# STM32F446RE_board.net
KiCad netlist of a schematic drawn in Altium Designer
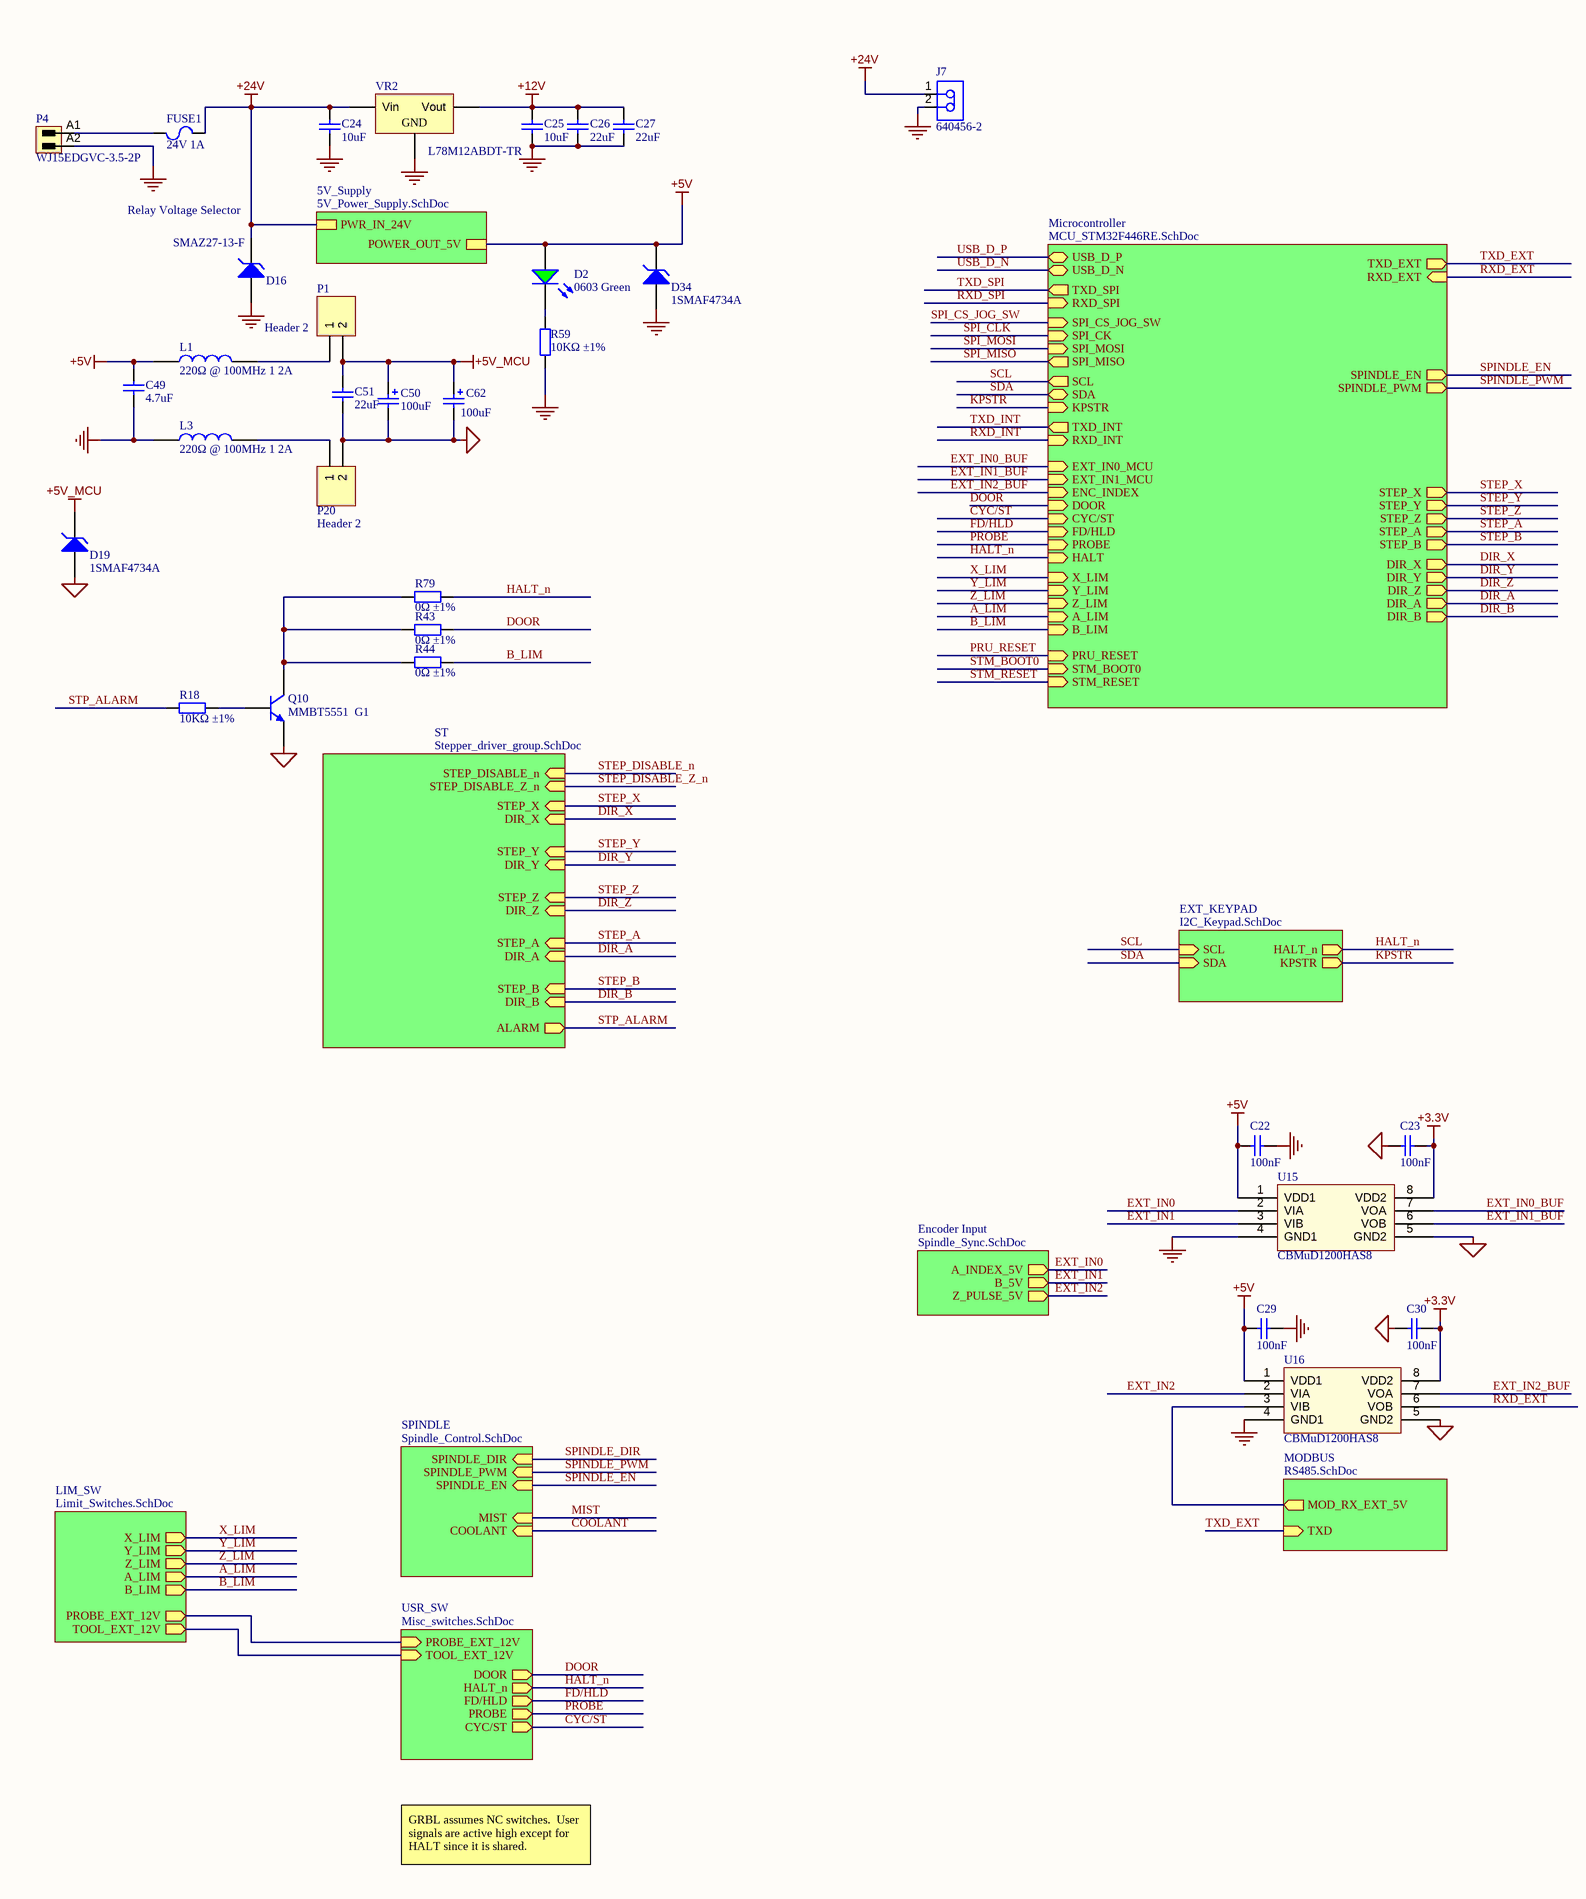
[diagram p0: STM32F446RE_board.SchDoc, left]
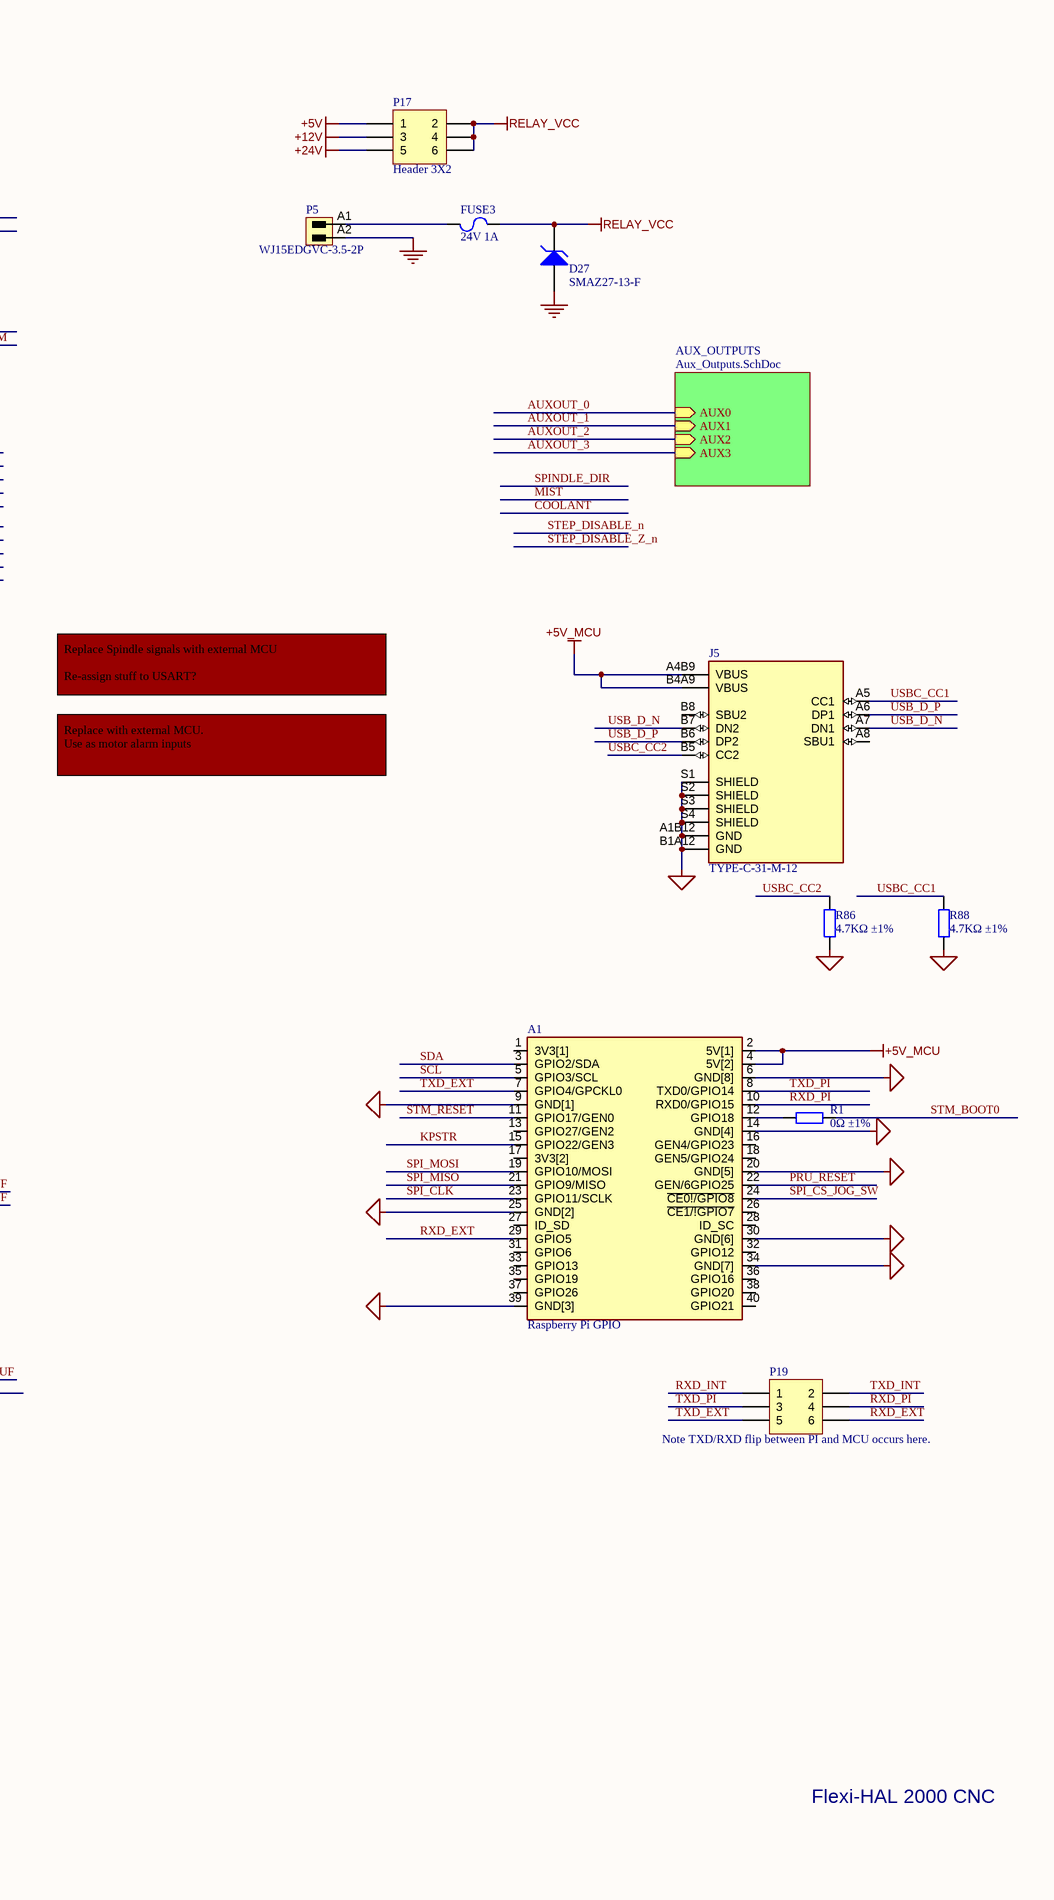
[diagram p1: STM32F446RE_board.SchDoc, right]

(export (version "E")
  (design (tool "Eeschema 10.0.6"))
  (components
    (comp (ref "A1")
      (value "Raspberry Pi GPIO")
      (footprint "MODULE_RASPBERRY_PI_4_MODEL_B")
      (description "Raspberry Pi Zero WH _Zero W with Headers_")
      (fields (field (name "MP") "DS1023-2*20SF11") (field (name "MF") "CONNFLY Elec"))
      (libsource (lib "Universal_CNC_Breakout") (part "ADA3708"))
    )
    (comp (ref "C22")
      (value "100nF")
      (footprint "0603_C")
      (description "Chip capacitors")
      (fields (field (name "MANUFACTURER") "YAGEO") (field (name "PARTNUMBER") "CC0603KRX7R9BB104"))
      (libsource (lib "Cap") (part "0603 100nF (104) 10% 50V"))
    )
    (comp (ref "C23")
      (value "100nF")
      (footprint "0603_C")
      (description "Chip capacitors")
      (fields (field (name "MANUFACTURER") "YAGEO") (field (name "PARTNUMBER") "CC0603KRX7R9BB104"))
      (libsource (lib "Cap") (part "0603 100nF (104) 10% 50V"))
    )
    (comp (ref "C24")
      (value "10uF")
      (footprint "1206_C")
      (description "Chip capacitors")
      (fields
        (field (name "MANUFACTURER") "Samsung Electro-Mechanics")
        (field (name "PARTNUMBER") "CL31A106KBHNNNE")
      )
      (libsource (lib "Cap") (part "1206 10uF (106) 10% 50V"))
    )
    (comp (ref "C25")
      (value "10uF")
      (footprint "1206_C")
      (description "Chip capacitors")
      (fields
        (field (name "MANUFACTURER") "Samsung Electro-Mechanics")
        (field (name "PARTNUMBER") "CL31A106KBHNNNE")
      )
      (libsource (lib "Cap") (part "1206 10uF (106) 10% 50V"))
    )
    (comp (ref "C26")
      (value "22uF")
      (footprint "0805_C")
      (description "Chip capacitors")
      (fields
        (field (name "MANUFACTURER") "Samsung Electro-Mechanics")
        (field (name "PARTNUMBER") "CL21A226MAQNNNE")
      )
      (libsource (lib "Cap") (part "0805 22uF (226) 20% 25V"))
    )
    (comp (ref "C27")
      (value "22uF")
      (footprint "0805_C")
      (description "Chip capacitors")
      (fields
        (field (name "MANUFACTURER") "Samsung Electro-Mechanics")
        (field (name "PARTNUMBER") "CL21A226MAQNNNE")
      )
      (libsource (lib "Cap") (part "0805 22uF (226) 20% 25V"))
    )
    (comp (ref "C29")
      (value "100nF")
      (footprint "0603_C")
      (description "Chip capacitors")
      (fields (field (name "MANUFACTURER") "YAGEO") (field (name "PARTNUMBER") "CC0603KRX7R9BB104"))
      (libsource (lib "Cap") (part "0603 100nF (104) 10% 50V"))
    )
    (comp (ref "C30")
      (value "100nF")
      (footprint "0603_C")
      (description "Chip capacitors")
      (fields (field (name "MANUFACTURER") "YAGEO") (field (name "PARTNUMBER") "CC0603KRX7R9BB104"))
      (libsource (lib "Cap") (part "0603 100nF (104) 10% 50V"))
    )
    (comp (ref "C49")
      (value "4.7uF")
      (footprint "0603_C")
      (description "Chip capacitors")
      (fields
        (field (name "MANUFACTURER") "Samsung Electro-Mechanics")
        (field (name "PARTNUMBER") "CL10A475KO8NNNC")
      )
      (libsource (lib "Cap") (part "0603 4.7uF (475) 10% 16V"))
    )
    (comp (ref "C50")
      (value "100uF")
      (footprint "CASE-B_3528")
      (description "Tantalum capacitor")
      (fields (field (name "MANUFACTURER") "AVX") (field (name "PARTNUMBER") "TAJB107K006RNJ"))
      (libsource (lib "Cap") (part "3528 100uF (107) 10% 6.3V"))
    )
    (comp (ref "C51")
      (value "22uF")
      (footprint "0805_C")
      (description "Chip capacitors")
      (fields
        (field (name "MANUFACTURER") "Samsung Electro-Mechanics")
        (field (name "PARTNUMBER") "CL21A226MAQNNNE")
      )
      (libsource (lib "Cap") (part "0805 22uF (226) 20% 25V"))
    )
    (comp (ref "C62")
      (value "100uF")
      (footprint "WCAP-ASLI_D6.3H7.7")
      (fields (field (name "MANUFACTURER") "Capxon International Elec"))
      (libsource (lib "IQAnalog") (part "865080445010"))
    )
    (comp (ref "D2")
      (value "0603 Green")
      (footprint "0603_LED_S1")
      (description "LED")
      (libsource (lib "LED") (part "0603 LED Green"))
    )
    (comp (ref "D16")
      (value "SMAZ27-13-F")
      (footprint "DIOM5226X240N")
      (description "27V ±5% 1W 500nA @ 20.5V SMA(DO-214AC) Zener Diodes RoHS")
      (libsource (lib "PrintNC_GRBLHAL_Breakout") (part "BZT52C27"))
    )
    (comp (ref "D19")
      (value "1SMAF4734A")
      (footprint "DIOM5226X240N")
      (description "27V ±5% 1W 500nA @ 20.5V SMA(DO-214AC) Zener Diodes RoHS")
      (libsource (lib "PrintNC_GRBLHAL_Breakout") (part "BZT52C27"))
    )
    (comp (ref "D27")
      (value "SMAZ27-13-F")
      (footprint "DIOM5226X240N")
      (description "27V ±5% 1W 500nA @ 20.5V SMA(DO-214AC) Zener Diodes RoHS")
      (libsource (lib "PrintNC_GRBLHAL_Breakout") (part "BZT52C27"))
    )
    (comp (ref "D34")
      (value "1SMAF4734A")
      (footprint "DIOM5226X240N")
      (description "27V ±5% 1W 500nA @ 20.5V SMA(DO-214AC) Zener Diodes RoHS")
      (libsource (lib "PrintNC_GRBLHAL_Breakout") (part "BZT52C27"))
    )
    (comp (ref "FUSE1")
      (value "24V 1A")
      (footprint "1206_C")
      (description "24V 1A 0.1s 1206 PTC Resettable Fuses RoHS")
      (fields
        (field (name "MANUFACTURER") "Jinrui Electronic Materials Co.")
        (field (name "PARTNUMBER") "JK-nSMD050-24")
      )
      (libsource (lib "PrintNC_GRBLHAL_Breakout") (part "JK-nSMD050-24"))
    )
    (comp (ref "FUSE3")
      (value "24V 1A")
      (footprint "1206_C")
      (description "24V 1A 0.1s 1206 PTC Resettable Fuses RoHS")
      (fields
        (field (name "MANUFACTURER") "Jinrui Electronic Materials Co.")
        (field (name "PARTNUMBER") "JK-nSMD050-24")
      )
      (libsource (lib "PrintNC_GRBLHAL_Breakout") (part "JK-nSMD050-24"))
    )
    (comp (ref "J5")
      (value "TYPE-C-31-M-12")
      (footprint "HRO_TYPE-C-31-M-12")
      (description "USB Connectors 24 Receptacle 1 8.94*7.3mm RoHS")
      (fields (field (name "MF") "HRO Electronics Co., Ltd."))
      (libsource (lib "Universal_CNC_Breakout") (part "TYPE-C-31-M-12"))
    )
    (comp (ref "J7")
      (value "640456-2")
      (footprint "TECO-640456-2_V")
      (fields (field (name "MANUFACTURER") "TE Connectivity"))
      (libsource (lib "Altium Content Vault") (part "CN-2P-F-QF2"))
    )
    (comp (ref "L1")
      (value "220Ω @ 100MHz 1 2A")
      (footprint "0805_C")
      (description "220Ω @ 100MHz 1 2A 150mΩ 0805 Ferrite Beads ROHS")
      (libsource (lib "FBEAD") (part "0402 220R@100Mhz 0.1A"))
    )
    (comp (ref "L3")
      (value "220Ω @ 100MHz 1 2A")
      (footprint "0805_C")
      (description "220Ω @ 100MHz 1 2A 150mΩ 0805 Ferrite Beads ROHS")
      (libsource (lib "FBEAD") (part "0402 220R@100Mhz 0.1A"))
    )
    (comp (ref "P1")
      (value "Header 2")
      (footprint "HDR1X2")
      (description "Header, 2-Pin")
      (fields (field (name "PUBLISHER") "Altium Limited"))
      (libsource (lib "Miscellaneous Connectors") (part "Header 2"))
    )
    (comp (ref "P4")
      (value "WJ15EDGVC-3.5-2P")
      (footprint "691321100002")
      (libsource (lib "Universal_CNC_Breakout") (part "3.5mm Terminal Header 2p"))
    )
    (comp (ref "P5")
      (value "WJ15EDGVC-3.5-2P")
      (footprint "691321100002")
      (fields (field (name "MANUFACTURER") "Weidmueller"))
      (libsource (lib "Universal_CNC_Breakout") (part "3.5mm Terminal Header 2p"))
    )
    (comp (ref "P17")
      (value "Header 3X2")
      (footprint "HDR2X3")
      (description "Header, 3-Pin, Dual row")
      (fields (field (name "PUBLISHER") "Altium Limited"))
      (libsource (lib "Miscellaneous Connectors") (part "Header 3X2"))
    )
    (comp (ref "P19")
      (value "Header 3X2")
      (footprint "HDR2X3")
      (description "Header, 3-Pin, Dual row")
      (fields (field (name "PUBLISHER") "Altium Limited"))
      (libsource (lib "Miscellaneous Connectors") (part "Header 3X2"))
    )
    (comp (ref "P20")
      (value "Header 2")
      (footprint "HDR1X2")
      (description "Header, 2-Pin")
      (fields (field (name "PUBLISHER") "Altium Limited"))
      (libsource (lib "") (part "Header 2_1"))
    )
    (comp (ref "Q10")
      (value "MMBT5551  G1")
      (footprint "SOT-23(SOT-23-3)")
      (description "三极管")
      (libsource (lib "PrintNC_GRBLHAL_Breakout") (part "SOT-23 MMBT5551  G1"))
    )
    (comp (ref "R1")
      (value "0Ω ±1%")
      (footprint "0603_R")
      (description "Chip resistor")
      (fields (field (name "MANUFACTURER") "Uniroyal Elec") (field (name "PARTNUMBER") "0603WAF0000T5E"))
      (libsource (lib "RES") (part "0603 0R (0R0) 1%"))
    )
    (comp (ref "R18")
      (value "10KΩ ±1%")
      (footprint "0603_R")
      (description "Chip resistor")
      (fields (field (name "MANUFACTURER") "Uniroyal Elec") (field (name "PARTNUMBER") "0603WAF1002T5E"))
      (libsource (lib "RES") (part "0603 10K (1002) 1%"))
    )
    (comp (ref "R43")
      (value "0Ω ±1%")
      (footprint "0603_R")
      (description "Chip resistor")
      (fields (field (name "MANUFACTURER") "Uniroyal Elec") (field (name "PARTNUMBER") "0603WAF0000T5E"))
      (libsource (lib "RES") (part "0603 0R (0R0) 1%"))
    )
    (comp (ref "R44")
      (value "0Ω ±1%")
      (footprint "0603_R")
      (description "Chip resistor")
      (fields (field (name "MANUFACTURER") "Uniroyal Elec") (field (name "PARTNUMBER") "0603WAF0000T5E"))
      (libsource (lib "RES") (part "0603 0R (0R0) 1%"))
    )
    (comp (ref "R59")
      (value "10KΩ ±1%")
      (footprint "0603_R")
      (description "Chip resistor")
      (fields (field (name "MANUFACTURER") "Uniroyal Elec") (field (name "PARTNUMBER") "0603WAF1002T5E"))
      (libsource (lib "") (part "0603 10K (1002) 1%_1"))
    )
    (comp (ref "R79")
      (value "0Ω ±1%")
      (footprint "0603_R")
      (description "Chip resistor")
      (fields (field (name "MANUFACTURER") "Uniroyal Elec") (field (name "PARTNUMBER") "0603WAF0000T5E"))
      (libsource (lib "RES") (part "0603 0R (0R0) 1%"))
    )
    (comp (ref "R86")
      (value "4.7KΩ ±1%")
      (footprint "0603_R")
      (description "Chip resistor")
      (fields (field (name "MANUFACTURER") "Uniroyal Elec") (field (name "PARTNUMBER") "0603WAF4701T5E"))
      (libsource (lib "RES") (part "0603 4.7K (4701) 1%"))
    )
    (comp (ref "R88")
      (value "4.7KΩ ±1%")
      (footprint "0603_R")
      (description "Chip resistor")
      (fields (field (name "MANUFACTURER") "Uniroyal Elec") (field (name "PARTNUMBER") "0603WAF4701T5E"))
      (libsource (lib "RES") (part "0603 4.7K (4701) 1%"))
    )
    (comp (ref "U15")
      (value "CBMuD1200HAS8")
      (footprint "SOIC-8_150mil")
      (description "Dual Channel Isolator")
      (libsource (lib "IC") (part "ADUM1201ARZ-RL7_[C9669]"))
    )
    (comp (ref "U16")
      (value "CBMuD1200HAS8")
      (footprint "SOIC-8_150mil")
      (description "Dual Channel Isolator")
      (libsource (lib "IC") (part "ADUM1201ARZ-RL7_[C9669]"))
    )
    (comp (ref "VR2")
      (value "L78M12ABDT-TR")
      (footprint "TO-252-2-180")
      (libsource (lib "PrintNC_GRBLHAL_Breakout") (part "TO-252-2 L78M05ABDT-TR"))
    )
  )
  (nets
    (net (code "1") (name "+3.3V") (class "Default")
      (node (ref "C23") (pin "2") (pinfunction "2_2") (pintype "passive"))
      (node (ref "C30") (pin "2") (pinfunction "2_2") (pintype "passive"))
      (node (ref "U15") (pin "8") (pinfunction "VDD2_8") (pintype "passive"))
      (node (ref "U16") (pin "8") (pinfunction "VDD2_8") (pintype "passive"))
    )
    (net (code "2") (name "+5V") (class "Default")
      (node (ref "C22") (pin "1") (pinfunction "1_1") (pintype "passive"))
      (node (ref "C29") (pin "1") (pinfunction "1_1") (pintype "passive"))
      (node (ref "C49") (pin "2") (pinfunction "2_2") (pintype "passive"))
      (node (ref "D2") (pin "A") (pinfunction "A_A") (pintype "passive"))
      (node (ref "D34") (pin "2") (pinfunction "K_2") (pintype "passive"))
      (node (ref "L1") (pin "1") (pinfunction "1_1") (pintype "passive"))
      (node (ref "P17") (pin "1") (pinfunction "1_1") (pintype "passive"))
      (node (ref "U15") (pin "1") (pinfunction "VDD1_1") (pintype "passive"))
      (node (ref "U16") (pin "1") (pinfunction "VDD1_1") (pintype "passive"))
    )
    (net (code "3") (name "+5V_MCU") (class "Default")
      (node (ref "A1") (pin "2") (pinfunction "5V[1]_2") (pintype "power_in"))
      (node (ref "A1") (pin "4") (pinfunction "5V[2]_4") (pintype "power_in"))
      (node (ref "C50") (pin "1") (pinfunction "1_1") (pintype "passive"))
      (node (ref "C51") (pin "2") (pinfunction "2_2") (pintype "passive"))
      (node (ref "C62") (pin "1") (pinfunction "P_1") (pintype "passive"))
      (node (ref "D19") (pin "2") (pinfunction "K_2") (pintype "passive"))
      (node (ref "J5") (pin "A4B9") (pinfunction "VBUS_A4B9") (pintype "power_in"))
      (node (ref "J5") (pin "B4A9") (pinfunction "VBUS_B4A9") (pintype "power_in"))
      (node (ref "P1") (pin "2") (pinfunction "2_2") (pintype "passive"))
    )
    (net (code "4") (name "+12V") (class "Default")
      (node (ref "C25") (pin "2") (pinfunction "2_2") (pintype "passive"))
      (node (ref "C26") (pin "2") (pinfunction "2_2") (pintype "passive"))
      (node (ref "C27") (pin "2") (pinfunction "2_2") (pintype "passive"))
      (node (ref "P17") (pin "3") (pinfunction "3_3") (pintype "passive"))
      (node (ref "VR2") (pin "3") (pinfunction "Vout_3") (pintype "passive"))
    )
    (net (code "5") (name "+24V") (class "Default")
      (node (ref "C24") (pin "2") (pinfunction "2_2") (pintype "passive"))
      (node (ref "D16") (pin "2") (pinfunction "K_2") (pintype "passive"))
      (node (ref "FUSE1") (pin "2") (pinfunction "2_2") (pintype "passive"))
      (node (ref "J7") (pin "1") (pinfunction "1_1") (pintype "passive"))
      (node (ref "P17") (pin "5") (pinfunction "5_5") (pintype "passive"))
      (node (ref "VR2") (pin "1") (pinfunction "Vin_1") (pintype "passive"))
    )
    (net (code "11") (name "/B_LIM") (class "Default")
      (node (ref "R44") (pin "1") (pinfunction "1_1") (pintype "passive"))
    )
    (net (code "19") (name "/DOOR") (class "Default")
      (node (ref "R43") (pin "1") (pinfunction "1_1") (pintype "passive"))
    )
    (net (code "20") (name "/EXT_IN0") (class "Default")
      (node (ref "U15") (pin "2") (pinfunction "VIA_2") (pintype "passive"))
    )
    (net (code "21") (name "/EXT_IN0_BUF") (class "Default")
      (node (ref "U15") (pin "7") (pinfunction "VOA_7") (pintype "passive"))
    )
    (net (code "22") (name "/EXT_IN1") (class "Default")
      (node (ref "U15") (pin "3") (pinfunction "VIB_3") (pintype "passive"))
    )
    (net (code "23") (name "/EXT_IN1_BUF") (class "Default")
      (node (ref "U15") (pin "6") (pinfunction "VOB_6") (pintype "passive"))
    )
    (net (code "24") (name "/EXT_IN2") (class "Default")
      (node (ref "U16") (pin "2") (pinfunction "VIA_2") (pintype "passive"))
    )
    (net (code "25") (name "/EXT_IN2_BUF") (class "Default")
      (node (ref "U16") (pin "7") (pinfunction "VOA_7") (pintype "passive"))
    )
    (net (code "27") (name "/HALT_n") (class "Default")
      (node (ref "R79") (pin "1") (pinfunction "1_1") (pintype "passive"))
    )
    (net (code "28") (name "/KPSTR") (class "Default")
      (node (ref "A1") (pin "15") (pinfunction "GPIO22/GEN3_15") (pintype "bidirectional"))
    )
    (net (code "30") (name "/MOD_RX_EXT_5V") (class "Default")
      (node (ref "U16") (pin "3") (pinfunction "VIB_3") (pintype "passive"))
    )
    (net (code "33") (name "/PRU_RESET") (class "Default")
      (node (ref "A1") (pin "22") (pinfunction "GEN/6GPIO25_22") (pintype "bidirectional"))
    )
    (net (code "34") (name "/RXD_EXT") (class "Default")
      (node (ref "A1") (pin "29") (pinfunction "GPIO5_29") (pintype "bidirectional"))
      (node (ref "P19") (pin "6") (pinfunction "6_6") (pintype "passive"))
      (node (ref "U16") (pin "6") (pinfunction "VOB_6") (pintype "passive"))
    )
    (net (code "35") (name "/RXD_INT") (class "Default")
      (node (ref "P19") (pin "1") (pinfunction "1_1") (pintype "passive"))
    )
    (net (code "36") (name "/RXD_PI") (class "Default")
      (node (ref "A1") (pin "10") (pinfunction "RXD0/GPIO15_10") (pintype "bidirectional"))
      (node (ref "P19") (pin "4") (pinfunction "4_4") (pintype "passive"))
    )
    (net (code "38") (name "/SCL") (class "Default")
      (node (ref "A1") (pin "5") (pinfunction "GPIO3/SCL_5") (pintype "bidirectional"))
    )
    (net (code "39") (name "/SDA") (class "Default")
      (node (ref "A1") (pin "3") (pinfunction "GPIO2/SDA_3") (pintype "bidirectional"))
    )
    (net (code "43") (name "/SPI_CLK") (class "Default")
      (node (ref "A1") (pin "23") (pinfunction "GPIO11/SCLK_23") (pintype "bidirectional"))
    )
    (net (code "44") (name "/SPI_CS_JOG_SW") (class "Default")
      (node (ref "A1") (pin "24") (pinfunction "~{CE0!/GPIO8}_24") (pintype "bidirectional"))
    )
    (net (code "45") (name "/SPI_MISO") (class "Default")
      (node (ref "A1") (pin "21") (pinfunction "GPIO9/MISO_21") (pintype "bidirectional"))
    )
    (net (code "46") (name "/SPI_MOSI") (class "Default")
      (node (ref "A1") (pin "19") (pinfunction "GPIO10/MOSI_19") (pintype "bidirectional"))
    )
    (net (code "54") (name "/STM_BOOT0") (class "Default")
      (node (ref "R1") (pin "1") (pinfunction "1_1") (pintype "passive"))
    )
    (net (code "55") (name "/STM_RESET") (class "Default")
      (node (ref "A1") (pin "11") (pinfunction "GPIO17/GEN0_11") (pintype "bidirectional"))
    )
    (net (code "56") (name "/STP_ALARM") (class "Default")
      (node (ref "R18") (pin "2") (pinfunction "2_2") (pintype "passive"))
    )
    (net (code "58") (name "/TXD_EXT") (class "Default")
      (node (ref "A1") (pin "7") (pinfunction "GPIO4/GPCKL0_7") (pintype "bidirectional"))
      (node (ref "P19") (pin "5") (pinfunction "5_5") (pintype "passive"))
    )
    (net (code "59") (name "/TXD_INT") (class "Default")
      (node (ref "P19") (pin "2") (pinfunction "2_2") (pintype "passive"))
    )
    (net (code "60") (name "/TXD_PI") (class "Default")
      (node (ref "A1") (pin "8") (pinfunction "TXD0/GPIO14_8") (pintype "bidirectional"))
      (node (ref "P19") (pin "3") (pinfunction "3_3") (pintype "passive"))
    )
    (net (code "62") (name "/USBC_CC1") (class "Default")
      (node (ref "J5") (pin "A5") (pinfunction "CC1_A5") (pintype "bidirectional"))
      (node (ref "R88") (pin "1") (pinfunction "1_1") (pintype "passive"))
    )
    (net (code "63") (name "/USBC_CC2") (class "Default")
      (node (ref "J5") (pin "B5") (pinfunction "CC2_B5") (pintype "bidirectional"))
      (node (ref "R86") (pin "1") (pinfunction "1_1") (pintype "passive"))
    )
    (net (code "64") (name "/USB_D_N") (class "Default")
      (node (ref "J5") (pin "A7") (pinfunction "DN1_A7") (pintype "bidirectional"))
      (node (ref "J5") (pin "B7") (pinfunction "DN2_B7") (pintype "bidirectional"))
    )
    (net (code "65") (name "/USB_D_P") (class "Default")
      (node (ref "J5") (pin "A6") (pinfunction "DP1_A6") (pintype "bidirectional"))
      (node (ref "J5") (pin "B6") (pinfunction "DP2_B6") (pintype "bidirectional"))
    )
    (net (code "69") (name "GND") (class "Default")
      (node (ref "C22") (pin "2") (pinfunction "2_2") (pintype "passive"))
      (node (ref "C24") (pin "1") (pinfunction "1_1") (pintype "passive"))
      (node (ref "C25") (pin "1") (pinfunction "1_1") (pintype "passive"))
      (node (ref "C26") (pin "1") (pinfunction "1_1") (pintype "passive"))
      (node (ref "C27") (pin "1") (pinfunction "1_1") (pintype "passive"))
      (node (ref "C29") (pin "2") (pinfunction "2_2") (pintype "passive"))
      (node (ref "C49") (pin "1") (pinfunction "1_1") (pintype "passive"))
      (node (ref "D16") (pin "1") (pinfunction "A_1") (pintype "passive"))
      (node (ref "D27") (pin "1") (pinfunction "A_1") (pintype "passive"))
      (node (ref "D34") (pin "1") (pinfunction "A_1") (pintype "passive"))
      (node (ref "J7") (pin "2") (pinfunction "2_2") (pintype "passive"))
      (node (ref "L3") (pin "1") (pinfunction "1_1") (pintype "passive"))
      (node (ref "P4") (pin "A2") (pinfunction "A2_A2") (pintype "passive"))
      (node (ref "P5") (pin "A2") (pinfunction "A2_A2") (pintype "passive"))
      (node (ref "R59") (pin "1") (pinfunction "1_1") (pintype "passive"))
      (node (ref "U15") (pin "4") (pinfunction "GND1_4") (pintype "passive"))
      (node (ref "U16") (pin "4") (pinfunction "GND1_4") (pintype "passive"))
      (node (ref "VR2") (pin "2") (pinfunction "GND_2") (pintype "passive"))
    )
    (net (code "70") (name "MCU_GND") (class "Default")
      (node (ref "A1") (pin "14") (pinfunction "GND[4]_14") (pintype "power_in"))
      (node (ref "A1") (pin "20") (pinfunction "GND[5]_20") (pintype "power_in"))
      (node (ref "A1") (pin "25") (pinfunction "GND[2]_25") (pintype "power_in"))
      (node (ref "A1") (pin "30") (pinfunction "GND[6]_30") (pintype "power_in"))
      (node (ref "A1") (pin "34") (pinfunction "GND[7]_34") (pintype "power_in"))
      (node (ref "A1") (pin "39") (pinfunction "GND[3]_39") (pintype "power_in"))
      (node (ref "A1") (pin "6") (pinfunction "GND[8]_6") (pintype "power_in"))
      (node (ref "A1") (pin "9") (pinfunction "GND[1]_9") (pintype "power_in"))
      (node (ref "C23") (pin "1") (pinfunction "1_1") (pintype "passive"))
      (node (ref "C30") (pin "1") (pinfunction "1_1") (pintype "passive"))
      (node (ref "C50") (pin "2") (pinfunction "2_2") (pintype "passive"))
      (node (ref "C51") (pin "1") (pinfunction "1_1") (pintype "passive"))
      (node (ref "C62") (pin "2") (pinfunction "N_2") (pintype "passive"))
      (node (ref "D19") (pin "1") (pinfunction "A_1") (pintype "passive"))
      (node (ref "J5") (pin "A1B12") (pinfunction "GND_A1B12") (pintype "power_in"))
      (node (ref "J5") (pin "B1A12") (pinfunction "GND_B1A12") (pintype "power_in"))
      (node (ref "J5") (pin "S1") (pinfunction "SHIELD_S1") (pintype "passive"))
      (node (ref "J5") (pin "S2") (pinfunction "SHIELD_S2") (pintype "passive"))
      (node (ref "J5") (pin "S3") (pinfunction "SHIELD_S3") (pintype "passive"))
      (node (ref "J5") (pin "S4") (pinfunction "SHIELD_S4") (pintype "passive"))
      (node (ref "P20") (pin "2") (pinfunction "2_2") (pintype "passive"))
      (node (ref "Q10") (pin "2") (pinfunction "E_2") (pintype "passive"))
      (node (ref "R86") (pin "2") (pinfunction "2_2") (pintype "passive"))
      (node (ref "R88") (pin "2") (pinfunction "2_2") (pintype "passive"))
      (node (ref "U15") (pin "5") (pinfunction "GND2_5") (pintype "passive"))
      (node (ref "U16") (pin "5") (pinfunction "GND2_5") (pintype "passive"))
    )
    (net (code "71") (name "Net-(A1-GPIO18)") (class "Default")
      (node (ref "A1") (pin "12") (pinfunction "GPIO18_12") (pintype "bidirectional"))
      (node (ref "R1") (pin "2") (pinfunction "2_2") (pintype "passive"))
    )
    (net (code "72") (name "Net-(D2-PadK)") (class "Default")
      (node (ref "D2") (pin "K") (pinfunction "K_K") (pintype "passive"))
      (node (ref "R59") (pin "2") (pinfunction "2_2") (pintype "passive"))
    )
    (net (code "73") (name "Net-(FUSE1-Pad1)") (class "Default")
      (node (ref "FUSE1") (pin "1") (pinfunction "1_1") (pintype "passive"))
      (node (ref "P4") (pin "A1") (pinfunction "A1_A1") (pintype "passive"))
    )
    (net (code "74") (name "Net-(FUSE3-Pad1)") (class "Default")
      (node (ref "FUSE3") (pin "1") (pinfunction "1_1") (pintype "passive"))
      (node (ref "P5") (pin "A1") (pinfunction "A1_A1") (pintype "passive"))
    )
    (net (code "75") (name "Net-(L1-Pad2)") (class "Default")
      (node (ref "L1") (pin "2") (pinfunction "2_2") (pintype "passive"))
      (node (ref "P1") (pin "1") (pinfunction "1_1") (pintype "passive"))
    )
    (net (code "76") (name "Net-(L3-Pad2)") (class "Default")
      (node (ref "L3") (pin "2") (pinfunction "2_2") (pintype "passive"))
      (node (ref "P20") (pin "1") (pinfunction "1_1") (pintype "passive"))
    )
    (net (code "77") (name "Net-(Q10-B)") (class "Default")
      (node (ref "Q10") (pin "1") (pinfunction "B_1") (pintype "passive"))
      (node (ref "R18") (pin "1") (pinfunction "1_1") (pintype "passive"))
    )
    (net (code "78") (name "Net-(Q10-C)") (class "Default")
      (node (ref "Q10") (pin "3") (pinfunction "C_3") (pintype "passive"))
      (node (ref "R43") (pin "2") (pinfunction "2_2") (pintype "passive"))
      (node (ref "R44") (pin "2") (pinfunction "2_2") (pintype "passive"))
      (node (ref "R79") (pin "2") (pinfunction "2_2") (pintype "passive"))
    )
    (net (code "79") (name "RELAY_VCC") (class "Default")
      (node (ref "D27") (pin "2") (pinfunction "K_2") (pintype "passive"))
      (node (ref "FUSE3") (pin "2") (pinfunction "2_2") (pintype "passive"))
      (node (ref "P17") (pin "2") (pinfunction "2_2") (pintype "passive"))
      (node (ref "P17") (pin "4") (pinfunction "4_4") (pintype "passive"))
      (node (ref "P17") (pin "6") (pinfunction "6_6") (pintype "passive"))
    )
    (net (code "80") (name "unconnected-(A1-3V3[1]-Pad1)") (class "Default")
      (node (ref "A1") (pin "1") (pinfunction "3V3[1]_1") (pintype "power_in"))
    )
    (net (code "81") (name "unconnected-(A1-3V3[2]-Pad17)") (class "Default")
      (node (ref "A1") (pin "17") (pinfunction "3V3[2]_17") (pintype "power_in"))
    )
    (net (code "82") (name "unconnected-(A1-GEN4{slash}GPIO23-Pad16)") (class "Default")
      (node (ref "A1") (pin "16") (pinfunction "GEN4/GPIO23_16") (pintype "bidirectional"))
    )
    (net (code "83") (name "unconnected-(A1-GEN5{slash}GPIO24-Pad18)") (class "Default")
      (node (ref "A1") (pin "18") (pinfunction "GEN5/GPIO24_18") (pintype "bidirectional"))
    )
    (net (code "84") (name "unconnected-(A1-GPIO6-Pad31)") (class "Default")
      (node (ref "A1") (pin "31") (pinfunction "GPIO6_31") (pintype "bidirectional"))
    )
    (net (code "85") (name "unconnected-(A1-GPIO12-Pad32)") (class "Default")
      (node (ref "A1") (pin "32") (pinfunction "GPIO12_32") (pintype "bidirectional"))
    )
    (net (code "86") (name "unconnected-(A1-GPIO13-Pad33)") (class "Default")
      (node (ref "A1") (pin "33") (pinfunction "GPIO13_33") (pintype "bidirectional"))
    )
    (net (code "87") (name "unconnected-(A1-GPIO16-Pad36)") (class "Default")
      (node (ref "A1") (pin "36") (pinfunction "GPIO16_36") (pintype "bidirectional"))
    )
    (net (code "88") (name "unconnected-(A1-GPIO19-Pad35)") (class "Default")
      (node (ref "A1") (pin "35") (pinfunction "GPIO19_35") (pintype "bidirectional"))
    )
    (net (code "89") (name "unconnected-(A1-GPIO20-Pad38)") (class "Default")
      (node (ref "A1") (pin "38") (pinfunction "GPIO20_38") (pintype "bidirectional"))
    )
    (net (code "90") (name "unconnected-(A1-GPIO21-Pad40)") (class "Default")
      (node (ref "A1") (pin "40") (pinfunction "GPIO21_40") (pintype "bidirectional"))
    )
    (net (code "91") (name "unconnected-(A1-GPIO26-Pad37)") (class "Default")
      (node (ref "A1") (pin "37") (pinfunction "GPIO26_37") (pintype "bidirectional"))
    )
    (net (code "92") (name "unconnected-(A1-GPIO27{slash}GEN2-Pad13)") (class "Default")
      (node (ref "A1") (pin "13") (pinfunction "GPIO27/GEN2_13") (pintype "bidirectional"))
    )
    (net (code "93") (name "unconnected-(A1-ID_SC-Pad28)") (class "Default")
      (node (ref "A1") (pin "28") (pinfunction "ID_SC_28") (pintype "bidirectional"))
    )
    (net (code "94") (name "unconnected-(A1-ID_SD-Pad27)") (class "Default")
      (node (ref "A1") (pin "27") (pinfunction "ID_SD_27") (pintype "bidirectional"))
    )
    (net (code "95") (name "unconnected-(A1-~{CE1{slash}!GPIO7}-Pad26)") (class "Default")
      (node (ref "A1") (pin "26") (pinfunction "~{CE1/!GPIO7}_26") (pintype "bidirectional"))
    )
    (net (code "96") (name "unconnected-(J5-SBU1-PadA8)") (class "Default")
      (node (ref "J5") (pin "A8") (pinfunction "SBU1_A8") (pintype "bidirectional"))
    )
    (net (code "97") (name "unconnected-(J5-SBU2-PadB8)") (class "Default")
      (node (ref "J5") (pin "B8") (pinfunction "SBU2_B8") (pintype "bidirectional"))
    )
  )
)
